# sevseg_interface.net
KiCad netlist of a schematic drawn in EAGLE
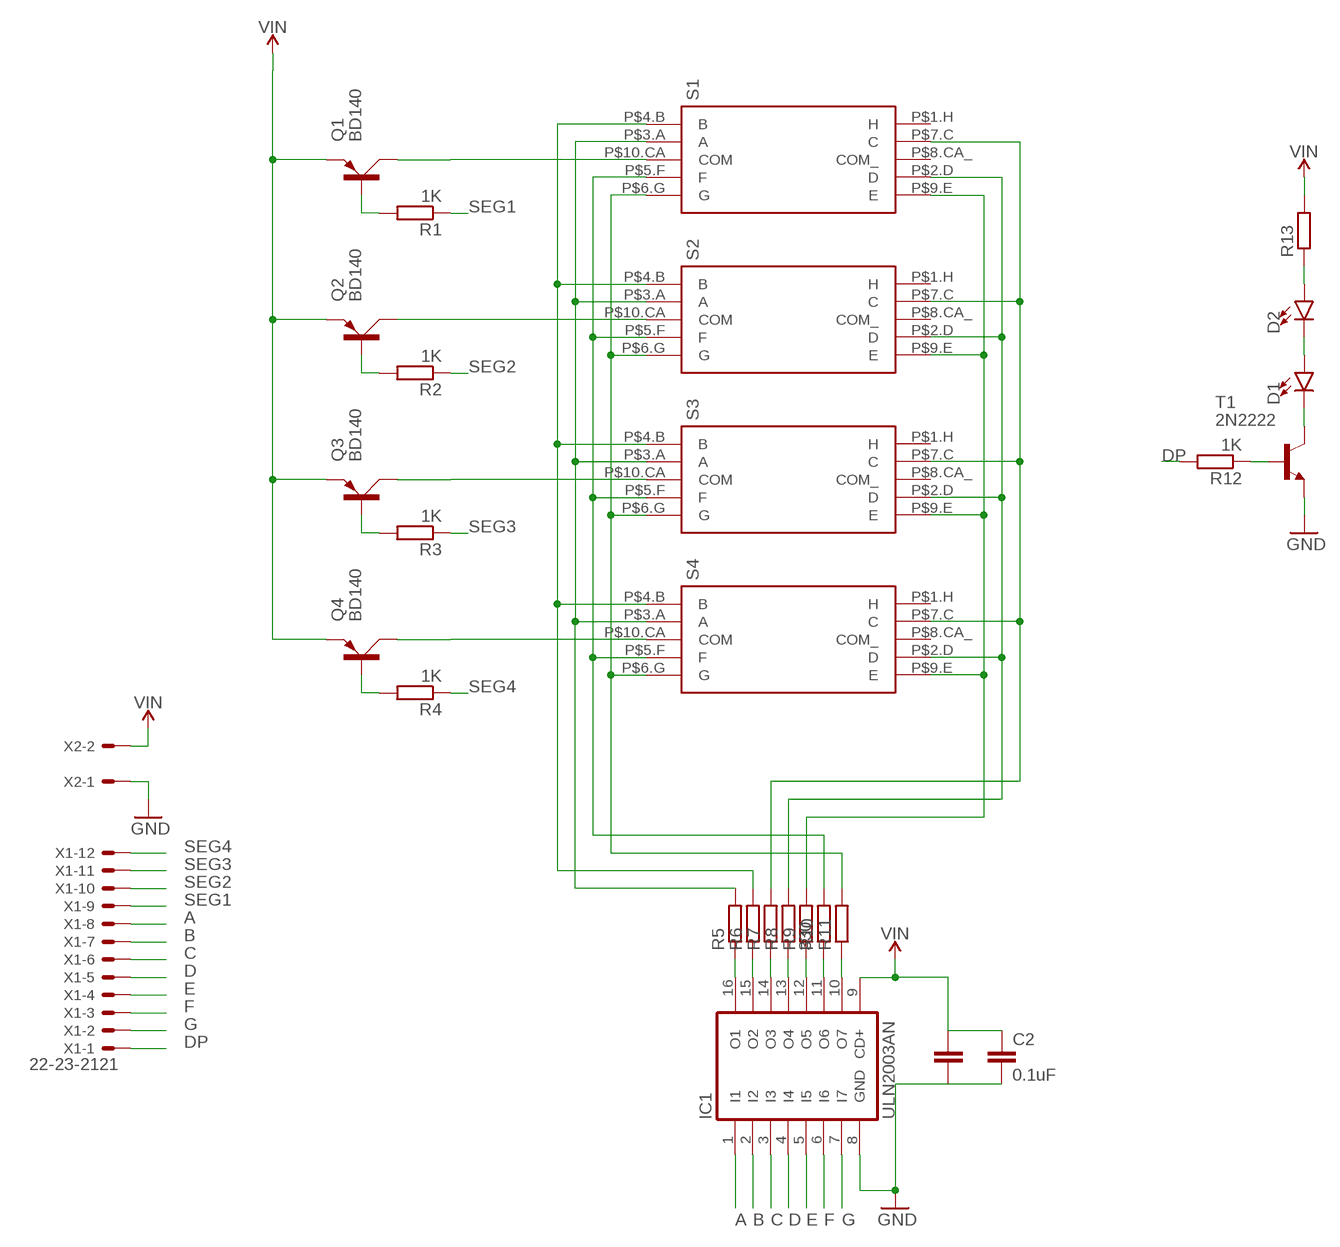
[diagram p0: schematic, sheet 1]

(export (version "E")
  (design (tool "Eeschema 10.0.6"))
  (components
    (comp (ref "C2")
      (value "0.1uF")
      (footprint "eagle-import:CAP-PTH-SMALL-KIT")
      (libsource (lib "eagle-import") (part "0.1UF-KIT-EZ-50V-20%"))
    )
    (comp (ref "D1")
      (value "LED5MM")
      (footprint "eagle-import:LED_5MM")
      (libsource (lib "eagle-import") (part "LED5MM"))
    )
    (comp (ref "D2")
      (value "LED5MM")
      (footprint "eagle-import:LED_5MM")
      (libsource (lib "eagle-import") (part "LED5MM"))
    )
    (comp (ref "IC1")
      (value "ULN2003AN")
      (footprint "eagle-import:DIL16")
      (libsource (lib "eagle-import") (part "ULN2003AN"))
    )
    (comp (ref "Q1")
      (value "BD140")
      (footprint "eagle-import:TO126AV")
      (libsource (lib "eagle-import") (part "BD140"))
    )
    (comp (ref "Q2")
      (value "BD140")
      (footprint "eagle-import:TO126AV")
      (libsource (lib "eagle-import") (part "BD140"))
    )
    (comp (ref "Q3")
      (value "BD140")
      (footprint "eagle-import:TO126AV")
      (libsource (lib "eagle-import") (part "BD140"))
    )
    (comp (ref "Q4")
      (value "BD140")
      (footprint "eagle-import:TO126AV")
      (libsource (lib "eagle-import") (part "BD140"))
    )
    (comp (ref "R1")
      (value "1K")
      (footprint "eagle-import:0204_7")
      (libsource (lib "eagle-import") (part "resistor_348_R-EU_0204/7"))
    )
    (comp (ref "R2")
      (value "1K")
      (footprint "eagle-import:0204_7")
      (libsource (lib "eagle-import") (part "resistor_348_R-EU_0204/7"))
    )
    (comp (ref "R3")
      (value "1K")
      (footprint "eagle-import:0204_7")
      (libsource (lib "eagle-import") (part "resistor_348_R-EU_0204/7"))
    )
    (comp (ref "R4")
      (value "1K")
      (footprint "eagle-import:0204_7")
      (libsource (lib "eagle-import") (part "resistor_348_R-EU_0204/7"))
    )
    (comp (ref "R5")
      (value "R-EU_0204/7")
      (footprint "eagle-import:0204_7")
      (libsource (lib "eagle-import") (part "R-EU_0204/7"))
    )
    (comp (ref "R6")
      (value "R-EU_0204/7")
      (footprint "eagle-import:0204_7")
      (libsource (lib "eagle-import") (part "R-EU_0204/7"))
    )
    (comp (ref "R7")
      (value "R-EU_0204/7")
      (footprint "eagle-import:0204_7")
      (libsource (lib "eagle-import") (part "R-EU_0204/7"))
    )
    (comp (ref "R8")
      (value "330")
      (footprint "eagle-import:0204_7")
      (libsource (lib "eagle-import") (part "R-EU_0204/7"))
    )
    (comp (ref "R9")
      (value "R-EU_0204/7")
      (footprint "eagle-import:0204_7")
      (libsource (lib "eagle-import") (part "R-EU_0204/7"))
    )
    (comp (ref "R10")
      (value "R-EU_0204/7")
      (footprint "eagle-import:0204_7")
      (libsource (lib "eagle-import") (part "R-EU_0204/7"))
    )
    (comp (ref "R11")
      (value "R-EU_0204/7")
      (footprint "eagle-import:0204_7")
      (libsource (lib "eagle-import") (part "R-EU_0204/7"))
    )
    (comp (ref "R12")
      (value "1K")
      (footprint "eagle-import:0204_7")
      (libsource (lib "eagle-import") (part "resistor_348_R-EU_0204/7"))
    )
    (comp (ref "R13")
      (value "R-EU_0204/7")
      (footprint "eagle-import:0204_7")
      (libsource (lib "eagle-import") (part "R-EU_0204/7"))
    )
    (comp (ref "S1")
      (value "7SEG_2.3IN_70MM_CA")
      (footprint "eagle-import:2.3INCH_70MM")
      (libsource (lib "eagle-import") (part "7SEG_2.3IN_70MM_CA"))
    )
    (comp (ref "S2")
      (value "7SEG_2.3IN_70MM_CA")
      (footprint "eagle-import:2.3INCH_70MM")
      (libsource (lib "eagle-import") (part "7SEG_2.3IN_70MM_CA"))
    )
    (comp (ref "S3")
      (value "7SEG_2.3IN_70MM_CA")
      (footprint "eagle-import:2.3INCH_70MM")
      (libsource (lib "eagle-import") (part "7SEG_2.3IN_70MM_CA"))
    )
    (comp (ref "S4")
      (value "7SEG_2.3IN_70MM_CA")
      (footprint "eagle-import:2.3INCH_70MM")
      (libsource (lib "eagle-import") (part "7SEG_2.3IN_70MM_CA"))
    )
    (comp (ref "T1")
      (value "2N2222")
      (footprint "eagle-import:TO18")
      (libsource (lib "eagle-import") (part "2N2222"))
    )
    (comp (ref "X1")
      (value "22-23-2121")
      (footprint "eagle-import:22-23-2121")
      (fields (field (name "MF") "MOLEX"))
      (libsource (lib "eagle-import") (part "22-23-2121"))
    )
    (comp (ref "X2")
      (value "KK-156-2")
      (footprint "eagle-import:KK-156-2")
      (fields (field (name "MF") "MOLEX"))
      (libsource (lib "eagle-import") (part "KK-156-2"))
    )
  )
  (nets
    (net (code "1") (name "/A") (class "Default")
      (node (ref "IC1") (pin "1") (pinfunction "I1_1") (pintype "input"))
      (node (ref "X1") (pin "8") (pinfunction "S_8") (pintype "passive"))
    )
    (net (code "2") (name "/B") (class "Default")
      (node (ref "IC1") (pin "2") (pinfunction "I2_2") (pintype "input"))
      (node (ref "X1") (pin "7") (pinfunction "S_7") (pintype "passive"))
    )
    (net (code "3") (name "/C") (class "Default")
      (node (ref "IC1") (pin "3") (pinfunction "I3_3") (pintype "input"))
      (node (ref "X1") (pin "6") (pinfunction "S_6") (pintype "passive"))
    )
    (net (code "4") (name "/D") (class "Default")
      (node (ref "IC1") (pin "4") (pinfunction "I4_4") (pintype "input"))
      (node (ref "X1") (pin "5") (pinfunction "S_5") (pintype "passive"))
    )
    (net (code "5") (name "/DP") (class "Default")
      (node (ref "R12") (pin "2") (pinfunction "2_2") (pintype "passive"))
      (node (ref "X1") (pin "1") (pinfunction "S_1") (pintype "passive"))
    )
    (net (code "6") (name "/E") (class "Default")
      (node (ref "IC1") (pin "5") (pinfunction "I5_5") (pintype "input"))
      (node (ref "X1") (pin "4") (pinfunction "S_4") (pintype "passive"))
    )
    (net (code "7") (name "/F") (class "Default")
      (node (ref "IC1") (pin "6") (pinfunction "I6_6") (pintype "input"))
      (node (ref "X1") (pin "3") (pinfunction "S_3") (pintype "passive"))
    )
    (net (code "8") (name "/G") (class "Default")
      (node (ref "IC1") (pin "7") (pinfunction "I7_7") (pintype "input"))
      (node (ref "X1") (pin "2") (pinfunction "S_2") (pintype "passive"))
    )
    (net (code "9") (name "/SEG1") (class "Default")
      (node (ref "R1") (pin "1") (pinfunction "1_1") (pintype "passive"))
      (node (ref "X1") (pin "9") (pinfunction "S_9") (pintype "passive"))
    )
    (net (code "10") (name "/SEG2") (class "Default")
      (node (ref "R2") (pin "1") (pinfunction "1_1") (pintype "passive"))
      (node (ref "X1") (pin "10") (pinfunction "S_10") (pintype "passive"))
    )
    (net (code "11") (name "/SEG3") (class "Default")
      (node (ref "R3") (pin "1") (pinfunction "1_1") (pintype "passive"))
      (node (ref "X1") (pin "11") (pinfunction "S_11") (pintype "passive"))
    )
    (net (code "12") (name "/SEG4") (class "Default")
      (node (ref "R4") (pin "1") (pinfunction "1_1") (pintype "passive"))
      (node (ref "X1") (pin "12") (pinfunction "S_12") (pintype "passive"))
    )
    (net (code "13") (name "GND") (class "Default")
      (node (ref "C2") (pin "2") (pinfunction "2_2") (pintype "passive"))
      (node (ref "IC1") (pin "8") (pinfunction "GND_8") (pintype "power_in"))
      (node (ref "T1") (pin "1") (pinfunction "E_1") (pintype "passive"))
      (node (ref "X2") (pin "1") (pinfunction "S_1") (pintype "passive"))
    )
    (net (code "14") (name "Net-(D1-C)") (class "Default")
      (node (ref "D1") (pin "K") (pinfunction "C_K") (pintype "passive"))
      (node (ref "T1") (pin "3") (pinfunction "C_3") (pintype "passive"))
    )
    (net (code "15") (name "Net-(D2-C)") (class "Default")
      (node (ref "D1") (pin "A") (pinfunction "A_A") (pintype "passive"))
      (node (ref "D2") (pin "K") (pinfunction "C_K") (pintype "passive"))
    )
    (net (code "16") (name "Net-(D2-PadA)") (class "Default")
      (node (ref "D2") (pin "A") (pinfunction "A_A") (pintype "passive"))
      (node (ref "R13") (pin "1") (pinfunction "1_1") (pintype "passive"))
    )
    (net (code "17") (name "Net-(IC1-O1)") (class "Default")
      (node (ref "IC1") (pin "16") (pinfunction "O1_16") (pintype "open_collector"))
      (node (ref "R5") (pin "1") (pinfunction "1_1") (pintype "passive"))
    )
    (net (code "18") (name "Net-(IC1-O2)") (class "Default")
      (node (ref "IC1") (pin "15") (pinfunction "O2_15") (pintype "open_collector"))
      (node (ref "R6") (pin "1") (pinfunction "1_1") (pintype "passive"))
    )
    (net (code "19") (name "Net-(IC1-O3)") (class "Default")
      (node (ref "IC1") (pin "14") (pinfunction "O3_14") (pintype "open_collector"))
      (node (ref "R7") (pin "1") (pinfunction "1_1") (pintype "passive"))
    )
    (net (code "20") (name "Net-(IC1-O4)") (class "Default")
      (node (ref "IC1") (pin "13") (pinfunction "O4_13") (pintype "open_collector"))
      (node (ref "R8") (pin "1") (pinfunction "1_1") (pintype "passive"))
    )
    (net (code "21") (name "Net-(IC1-O5)") (class "Default")
      (node (ref "IC1") (pin "12") (pinfunction "O5_12") (pintype "open_collector"))
      (node (ref "R9") (pin "1") (pinfunction "1_1") (pintype "passive"))
    )
    (net (code "22") (name "Net-(IC1-O6)") (class "Default")
      (node (ref "IC1") (pin "11") (pinfunction "O6_11") (pintype "open_collector"))
      (node (ref "R10") (pin "1") (pinfunction "1_1") (pintype "passive"))
    )
    (net (code "23") (name "Net-(IC1-O7)") (class "Default")
      (node (ref "IC1") (pin "10") (pinfunction "O7_10") (pintype "open_collector"))
      (node (ref "R11") (pin "1") (pinfunction "1_1") (pintype "passive"))
    )
    (net (code "24") (name "Net-(Q1-PadB)") (class "Default")
      (node (ref "Q1") (pin "B") (pinfunction "B_B") (pintype "passive"))
      (node (ref "R1") (pin "2") (pinfunction "2_2") (pintype "passive"))
    )
    (net (code "25") (name "Net-(Q2-PadB)") (class "Default")
      (node (ref "Q2") (pin "B") (pinfunction "B_B") (pintype "passive"))
      (node (ref "R2") (pin "2") (pinfunction "2_2") (pintype "passive"))
    )
    (net (code "26") (name "Net-(Q3-PadB)") (class "Default")
      (node (ref "Q3") (pin "B") (pinfunction "B_B") (pintype "passive"))
      (node (ref "R3") (pin "2") (pinfunction "2_2") (pintype "passive"))
    )
    (net (code "27") (name "Net-(Q4-PadB)") (class "Default")
      (node (ref "Q4") (pin "B") (pinfunction "B_B") (pintype "passive"))
      (node (ref "R4") (pin "2") (pinfunction "2_2") (pintype "passive"))
    )
    (net (code "28") (name "Net-(S1-A)") (class "Default")
      (node (ref "R5") (pin "2") (pinfunction "2_2") (pintype "passive"))
      (node (ref "S1") (pin "P$3.A") (pinfunction "A_P$3.A") (pintype "bidirectional"))
      (node (ref "S2") (pin "P$3.A") (pinfunction "A_P$3.A") (pintype "bidirectional"))
      (node (ref "S3") (pin "P$3.A") (pinfunction "A_P$3.A") (pintype "bidirectional"))
      (node (ref "S4") (pin "P$3.A") (pinfunction "A_P$3.A") (pintype "bidirectional"))
    )
    (net (code "29") (name "Net-(S1-B)") (class "Default")
      (node (ref "R6") (pin "2") (pinfunction "2_2") (pintype "passive"))
      (node (ref "S1") (pin "P$4.B") (pinfunction "B_P$4.B") (pintype "bidirectional"))
      (node (ref "S2") (pin "P$4.B") (pinfunction "B_P$4.B") (pintype "bidirectional"))
      (node (ref "S3") (pin "P$4.B") (pinfunction "B_P$4.B") (pintype "bidirectional"))
      (node (ref "S4") (pin "P$4.B") (pinfunction "B_P$4.B") (pintype "bidirectional"))
    )
    (net (code "30") (name "Net-(S1-C)") (class "Default")
      (node (ref "R7") (pin "2") (pinfunction "2_2") (pintype "passive"))
      (node (ref "S1") (pin "P$7.C") (pinfunction "C_P$7.C") (pintype "bidirectional"))
      (node (ref "S2") (pin "P$7.C") (pinfunction "C_P$7.C") (pintype "bidirectional"))
      (node (ref "S3") (pin "P$7.C") (pinfunction "C_P$7.C") (pintype "bidirectional"))
      (node (ref "S4") (pin "P$7.C") (pinfunction "C_P$7.C") (pintype "bidirectional"))
    )
    (net (code "31") (name "Net-(S1-COM)") (class "Default")
      (node (ref "Q1") (pin "C") (pinfunction "C_C") (pintype "passive"))
      (node (ref "S1") (pin "P$10.CA") (pinfunction "COM_P$10.CA") (pintype "bidirectional"))
    )
    (net (code "32") (name "Net-(S1-D)") (class "Default")
      (node (ref "R8") (pin "2") (pinfunction "2_2") (pintype "passive"))
      (node (ref "S1") (pin "P$2.D") (pinfunction "D_P$2.D") (pintype "bidirectional"))
      (node (ref "S2") (pin "P$2.D") (pinfunction "D_P$2.D") (pintype "bidirectional"))
      (node (ref "S3") (pin "P$2.D") (pinfunction "D_P$2.D") (pintype "bidirectional"))
      (node (ref "S4") (pin "P$2.D") (pinfunction "D_P$2.D") (pintype "bidirectional"))
    )
    (net (code "33") (name "Net-(S1-E)") (class "Default")
      (node (ref "R9") (pin "2") (pinfunction "2_2") (pintype "passive"))
      (node (ref "S1") (pin "P$9.E") (pinfunction "E_P$9.E") (pintype "bidirectional"))
      (node (ref "S2") (pin "P$9.E") (pinfunction "E_P$9.E") (pintype "bidirectional"))
      (node (ref "S3") (pin "P$9.E") (pinfunction "E_P$9.E") (pintype "bidirectional"))
      (node (ref "S4") (pin "P$9.E") (pinfunction "E_P$9.E") (pintype "bidirectional"))
    )
    (net (code "34") (name "Net-(S1-F)") (class "Default")
      (node (ref "R10") (pin "2") (pinfunction "2_2") (pintype "passive"))
      (node (ref "S1") (pin "P$5.F") (pinfunction "F_P$5.F") (pintype "bidirectional"))
      (node (ref "S2") (pin "P$5.F") (pinfunction "F_P$5.F") (pintype "bidirectional"))
      (node (ref "S3") (pin "P$5.F") (pinfunction "F_P$5.F") (pintype "bidirectional"))
      (node (ref "S4") (pin "P$5.F") (pinfunction "F_P$5.F") (pintype "bidirectional"))
    )
    (net (code "35") (name "Net-(S1-G)") (class "Default")
      (node (ref "R11") (pin "2") (pinfunction "2_2") (pintype "passive"))
      (node (ref "S1") (pin "P$6.G") (pinfunction "G_P$6.G") (pintype "bidirectional"))
      (node (ref "S2") (pin "P$6.G") (pinfunction "G_P$6.G") (pintype "bidirectional"))
      (node (ref "S3") (pin "P$6.G") (pinfunction "G_P$6.G") (pintype "bidirectional"))
      (node (ref "S4") (pin "P$6.G") (pinfunction "G_P$6.G") (pintype "bidirectional"))
    )
    (net (code "36") (name "Net-(S2-COM)") (class "Default")
      (node (ref "Q2") (pin "C") (pinfunction "C_C") (pintype "passive"))
      (node (ref "S2") (pin "P$10.CA") (pinfunction "COM_P$10.CA") (pintype "bidirectional"))
    )
    (net (code "37") (name "Net-(S3-COM)") (class "Default")
      (node (ref "Q3") (pin "C") (pinfunction "C_C") (pintype "passive"))
      (node (ref "S3") (pin "P$10.CA") (pinfunction "COM_P$10.CA") (pintype "bidirectional"))
    )
    (net (code "38") (name "Net-(S4-COM)") (class "Default")
      (node (ref "Q4") (pin "C") (pinfunction "C_C") (pintype "passive"))
      (node (ref "S4") (pin "P$10.CA") (pinfunction "COM_P$10.CA") (pintype "bidirectional"))
    )
    (net (code "39") (name "Net-(T1-B)") (class "Default")
      (node (ref "R12") (pin "1") (pinfunction "1_1") (pintype "passive"))
      (node (ref "T1") (pin "2") (pinfunction "B_2") (pintype "passive"))
    )
    (net (code "40") (name "VIN") (class "Default")
      (node (ref "C2") (pin "1") (pinfunction "1_1") (pintype "passive"))
      (node (ref "IC1") (pin "9") (pinfunction "CD+_9") (pintype "passive"))
      (node (ref "Q1") (pin "E") (pinfunction "E_E") (pintype "passive"))
      (node (ref "Q2") (pin "E") (pinfunction "E_E") (pintype "passive"))
      (node (ref "Q3") (pin "E") (pinfunction "E_E") (pintype "passive"))
      (node (ref "Q4") (pin "E") (pinfunction "E_E") (pintype "passive"))
      (node (ref "R13") (pin "2") (pinfunction "2_2") (pintype "passive"))
      (node (ref "X2") (pin "2") (pinfunction "S_2") (pintype "passive"))
    )
    (net (code "41") (name "unconnected-(S1-COM_-PadP$8.CA_)") (class "Default")
      (node (ref "S1") (pin "P$8.CA_") (pinfunction "COM__P$8.CA_") (pintype "bidirectional"))
    )
    (net (code "42") (name "unconnected-(S1-H-PadP$1.H)") (class "Default")
      (node (ref "S1") (pin "P$1.H") (pinfunction "H_P$1.H") (pintype "bidirectional"))
    )
    (net (code "43") (name "unconnected-(S2-COM_-PadP$8.CA_)") (class "Default")
      (node (ref "S2") (pin "P$8.CA_") (pinfunction "COM__P$8.CA_") (pintype "bidirectional"))
    )
    (net (code "44") (name "unconnected-(S2-H-PadP$1.H)") (class "Default")
      (node (ref "S2") (pin "P$1.H") (pinfunction "H_P$1.H") (pintype "bidirectional"))
    )
    (net (code "45") (name "unconnected-(S3-COM_-PadP$8.CA_)") (class "Default")
      (node (ref "S3") (pin "P$8.CA_") (pinfunction "COM__P$8.CA_") (pintype "bidirectional"))
    )
    (net (code "46") (name "unconnected-(S3-H-PadP$1.H)") (class "Default")
      (node (ref "S3") (pin "P$1.H") (pinfunction "H_P$1.H") (pintype "bidirectional"))
    )
    (net (code "47") (name "unconnected-(S4-COM_-PadP$8.CA_)") (class "Default")
      (node (ref "S4") (pin "P$8.CA_") (pinfunction "COM__P$8.CA_") (pintype "bidirectional"))
    )
    (net (code "48") (name "unconnected-(S4-H-PadP$1.H)") (class "Default")
      (node (ref "S4") (pin "P$1.H") (pinfunction "H_P$1.H") (pintype "bidirectional"))
    )
  )
)
